# avr.net
KiCad netlist of a schematic drawn in EAGLE
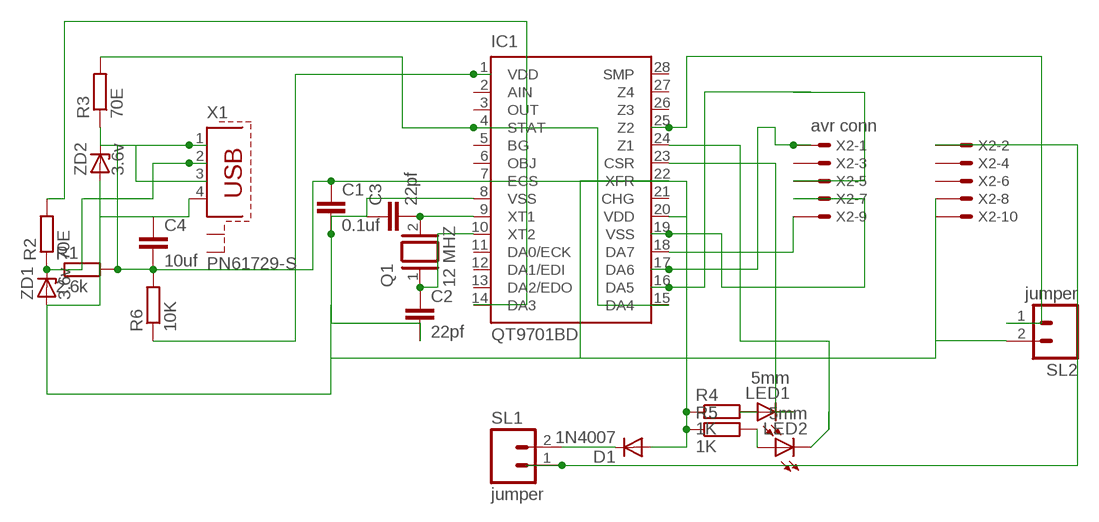
[diagram p0: schematic, sheet 1]

(export (version "E")
  (design (tool "Eeschema 10.0.6"))
  (components
    (comp (ref "C1")
      (value "0.1uf")
      (footprint "eagle-import:C2.5-3")
      (libsource (lib "eagle-import") (part "C2,5-3"))
    )
    (comp (ref "C2")
      (value "22pf")
      (footprint "eagle-import:C2.5-3")
      (libsource (lib "eagle-import") (part "C2,5-3"))
    )
    (comp (ref "C3")
      (value "22pf")
      (footprint "eagle-import:C2.5-3")
      (libsource (lib "eagle-import") (part "C2,5-3"))
    )
    (comp (ref "C4")
      (value "10uf")
      (footprint "eagle-import:C2.5-3")
      (libsource (lib "eagle-import") (part "C2,5-3"))
    )
    (comp (ref "D1")
      (value "1N4007")
      (footprint "eagle-import:DO41-10")
      (libsource (lib "eagle-import") (part "1N4004"))
    )
    (comp (ref "IC1")
      (value "QT9701BD")
      (footprint "eagle-import:DIL28-3")
      (libsource (lib "eagle-import") (part "QT9701BD"))
    )
    (comp (ref "LED1")
      (value "5mm")
      (footprint "eagle-import:LED5MM")
      (libsource (lib "eagle-import") (part "LED5MM"))
    )
    (comp (ref "LED2")
      (value "5mm")
      (footprint "eagle-import:LED5MM")
      (libsource (lib "eagle-import") (part "LED5MM"))
    )
    (comp (ref "Q1")
      (value "12 MHZ")
      (footprint "eagle-import:QS")
      (libsource (lib "eagle-import") (part "XTAL/S"))
    )
    (comp (ref "R1")
      (value "2.6k")
      (footprint "eagle-import:0204_7")
      (libsource (lib "eagle-import") (part "R-EU_0204/7"))
    )
    (comp (ref "R2")
      (value "70E")
      (footprint "eagle-import:0204_7")
      (libsource (lib "eagle-import") (part "R-EU_0204/7"))
    )
    (comp (ref "R3")
      (value "70E")
      (footprint "eagle-import:0204_7")
      (libsource (lib "eagle-import") (part "R-EU_0204/7"))
    )
    (comp (ref "R4")
      (value "1K")
      (footprint "eagle-import:0204_7")
      (libsource (lib "eagle-import") (part "R-EU_0204/7"))
    )
    (comp (ref "R5")
      (value "1K")
      (footprint "eagle-import:0204_7")
      (libsource (lib "eagle-import") (part "R-EU_0204/7"))
    )
    (comp (ref "R6")
      (value "10K")
      (footprint "eagle-import:0204_7")
      (libsource (lib "eagle-import") (part "R-EU_0204/7"))
    )
    (comp (ref "SL1")
      (value "jumper")
      (footprint "eagle-import:02P")
      (libsource (lib "eagle-import") (part "M02"))
    )
    (comp (ref "SL2")
      (value "jumper")
      (footprint "eagle-import:02P")
      (libsource (lib "eagle-import") (part "M02"))
    )
    (comp (ref "X1")
      (value "PN61729-S")
      (footprint "eagle-import:PN61729-S")
      (libsource (lib "eagle-import") (part "PN61729-S"))
    )
    (comp (ref "X2")
      (value "avr conn")
      (footprint "eagle-import:057-010-1")
      (libsource (lib "eagle-import") (part "057-010-1"))
    )
    (comp (ref "ZD1")
      (value "3.6v")
      (footprint "eagle-import:SOD81")
      (libsource (lib "eagle-import") (part "BZD23"))
    )
    (comp (ref "ZD2")
      (value "3.6v")
      (footprint "eagle-import:SOD81")
      (libsource (lib "eagle-import") (part "BZD23"))
    )
  )
  (nets
    (net (code "1") (name "Net-(D1-PadC)") (class "Default")
      (node (ref "D1") (pin "C") (pinfunction "C_C") (pintype "passive"))
      (node (ref "SL1") (pin "2") (pinfunction "2_2") (pintype "passive"))
    )
    (net (code "2") (name "Net-(IC1-CSR)") (class "Default")
      (node (ref "IC1") (pin "23") (pinfunction "CSR_23") (pintype "output"))
      (node (ref "LED1") (pin "K") (pinfunction "C_K") (pintype "passive"))
    )
    (net (code "3") (name "Net-(IC1-DA3)") (class "Default")
      (node (ref "IC1") (pin "14") (pinfunction "DA3_14") (pintype "output"))
      (node (ref "R2") (pin "2") (pinfunction "2_2") (pintype "passive"))
    )
    (net (code "4") (name "Net-(IC1-DA4)") (class "Default")
      (node (ref "IC1") (pin "15") (pinfunction "DA4_15") (pintype "output"))
      (node (ref "IC1") (pin "4") (pinfunction "STAT_4") (pintype "output"))
      (node (ref "R3") (pin "2") (pinfunction "2_2") (pintype "passive"))
    )
    (net (code "5") (name "Net-(IC1-DA5)") (class "Default")
      (node (ref "IC1") (pin "16") (pinfunction "DA5_16") (pintype "output"))
      (node (ref "X2") (pin "5") (pinfunction "S_5") (pintype "passive"))
    )
    (net (code "6") (name "Net-(IC1-DA6)") (class "Default")
      (node (ref "IC1") (pin "17") (pinfunction "DA6_17") (pintype "output"))
      (node (ref "X2") (pin "1") (pinfunction "S_1") (pintype "passive"))
    )
    (net (code "7") (name "Net-(IC1-DA7)") (class "Default")
      (node (ref "IC1") (pin "18") (pinfunction "DA7_18") (pintype "output"))
      (node (ref "X2") (pin "9") (pinfunction "S_9") (pintype "passive"))
    )
    (net (code "8") (name "Net-(IC1-ECS)") (class "Default")
      (node (ref "C1") (pin "1") (pinfunction "1_1") (pintype "passive"))
      (node (ref "C4") (pin "2") (pinfunction "2_2") (pintype "passive"))
      (node (ref "D1") (pin "A") (pinfunction "A_A") (pintype "passive"))
      (node (ref "IC1") (pin "20") (pinfunction "VDD_20") (pintype "input"))
      (node (ref "IC1") (pin "7") (pinfunction "ECS_7") (pintype "output"))
      (node (ref "R1") (pin "2") (pinfunction "2_2") (pintype "passive"))
      (node (ref "R4") (pin "1") (pinfunction "1_1") (pintype "passive"))
      (node (ref "R5") (pin "1") (pinfunction "1_1") (pintype "passive"))
      (node (ref "R6") (pin "2") (pinfunction "2_2") (pintype "passive"))
      (node (ref "X1") (pin "1") (pinfunction "1_1") (pintype "passive"))
    )
    (net (code "9") (name "Net-(IC1-VDD-Pad1)") (class "Default")
      (node (ref "IC1") (pin "1") (pinfunction "VDD_1") (pintype "input"))
      (node (ref "R6") (pin "1") (pinfunction "1_1") (pintype "passive"))
    )
    (net (code "10") (name "Net-(IC1-XFR)") (class "Default")
      (node (ref "C1") (pin "2") (pinfunction "2_2") (pintype "passive"))
      (node (ref "C2") (pin "2") (pinfunction "2_2") (pintype "passive"))
      (node (ref "C3") (pin "1") (pinfunction "1_1") (pintype "passive"))
      (node (ref "C4") (pin "1") (pinfunction "1_1") (pintype "passive"))
      (node (ref "IC1") (pin "22") (pinfunction "XFR_22") (pintype "output"))
      (node (ref "IC1") (pin "8") (pinfunction "VSS_8") (pintype "input"))
      (node (ref "SL2") (pin "2") (pinfunction "2_2") (pintype "passive"))
      (node (ref "X1") (pin "4") (pinfunction "4_4") (pintype "passive"))
      (node (ref "X2") (pin "10") (pinfunction "S_10") (pintype "passive"))
      (node (ref "X2") (pin "8") (pinfunction "S_8") (pintype "passive"))
      (node (ref "ZD1") (pin "A") (pinfunction "A_A") (pintype "passive"))
      (node (ref "ZD2") (pin "A") (pinfunction "A_A") (pintype "passive"))
    )
    (net (code "11") (name "Net-(IC1-XT1)") (class "Default")
      (node (ref "C3") (pin "2") (pinfunction "2_2") (pintype "passive"))
      (node (ref "IC1") (pin "9") (pinfunction "XT1_9") (pintype "input"))
      (node (ref "Q1") (pin "2") (pinfunction "2_2") (pintype "passive"))
    )
    (net (code "12") (name "Net-(IC1-XT2)") (class "Default")
      (node (ref "C2") (pin "1") (pinfunction "1_1") (pintype "passive"))
      (node (ref "IC1") (pin "10") (pinfunction "XT2_10") (pintype "output"))
      (node (ref "Q1") (pin "1") (pinfunction "1_1") (pintype "passive"))
    )
    (net (code "13") (name "Net-(IC1-Z1)") (class "Default")
      (node (ref "IC1") (pin "24") (pinfunction "Z1_24") (pintype "output"))
      (node (ref "LED2") (pin "K") (pinfunction "C_K") (pintype "passive"))
    )
    (net (code "14") (name "Net-(IC1-Z2)") (class "Default")
      (node (ref "IC1") (pin "25") (pinfunction "Z2_25") (pintype "output"))
      (node (ref "SL2") (pin "1") (pinfunction "1_1") (pintype "passive"))
    )
    (net (code "15") (name "Net-(LED1-PadA)") (class "Default")
      (node (ref "LED1") (pin "A") (pinfunction "A_A") (pintype "passive"))
      (node (ref "R4") (pin "2") (pinfunction "2_2") (pintype "passive"))
    )
    (net (code "16") (name "Net-(LED2-PadA)") (class "Default")
      (node (ref "LED2") (pin "A") (pinfunction "A_A") (pintype "passive"))
      (node (ref "R5") (pin "2") (pinfunction "2_2") (pintype "passive"))
    )
    (net (code "17") (name "Net-(R1-Pad1)") (class "Default")
      (node (ref "R1") (pin "1") (pinfunction "1_1") (pintype "passive"))
      (node (ref "R2") (pin "1") (pinfunction "1_1") (pintype "passive"))
      (node (ref "X1") (pin "2") (pinfunction "2_2") (pintype "passive"))
      (node (ref "ZD1") (pin "C") (pinfunction "C_C") (pintype "passive"))
    )
    (net (code "18") (name "Net-(R3-Pad1)") (class "Default")
      (node (ref "R3") (pin "1") (pinfunction "1_1") (pintype "passive"))
      (node (ref "X1") (pin "3") (pinfunction "3_3") (pintype "passive"))
      (node (ref "ZD2") (pin "C") (pinfunction "C_C") (pintype "passive"))
    )
    (net (code "19") (name "Net-(X2C-S)") (class "Default")
      (node (ref "SL1") (pin "1") (pinfunction "1_1") (pintype "passive"))
      (node (ref "X2") (pin "2") (pinfunction "S_2") (pintype "passive"))
    )
    (net (code "20") (name "Net-(X2H-S)") (class "Default")
      (node (ref "IC1") (pin "19") (pinfunction "VSS_19") (pintype "input"))
      (node (ref "X2") (pin "7") (pinfunction "S_7") (pintype "passive"))
    )
    (net (code "21") (name "unconnected-(IC1-AIN-Pad2)") (class "Default")
      (node (ref "IC1") (pin "2") (pinfunction "AIN_2") (pintype "input"))
    )
    (net (code "22") (name "unconnected-(IC1-BG-Pad5)") (class "Default")
      (node (ref "IC1") (pin "5") (pinfunction "BG_5") (pintype "input"))
    )
    (net (code "23") (name "unconnected-(IC1-CHG-Pad21)") (class "Default")
      (node (ref "IC1") (pin "21") (pinfunction "CHG_21") (pintype "output"))
    )
    (net (code "24") (name "unconnected-(IC1-DA0{slash}ECK-Pad11)") (class "Default")
      (node (ref "IC1") (pin "11") (pinfunction "DA0/ECK_11") (pintype "output"))
    )
    (net (code "25") (name "unconnected-(IC1-DA1{slash}EDI-Pad12)") (class "Default")
      (node (ref "IC1") (pin "12") (pinfunction "DA1/EDI_12") (pintype "output"))
    )
    (net (code "26") (name "unconnected-(IC1-DA2{slash}EDO-Pad13)") (class "Default")
      (node (ref "IC1") (pin "13") (pinfunction "DA2/EDO_13") (pintype "output"))
    )
    (net (code "27") (name "unconnected-(IC1-OBJ-Pad6)") (class "Default")
      (node (ref "IC1") (pin "6") (pinfunction "OBJ_6") (pintype "input"))
    )
    (net (code "28") (name "unconnected-(IC1-OUT-Pad3)") (class "Default")
      (node (ref "IC1") (pin "3") (pinfunction "OUT_3") (pintype "output"))
    )
    (net (code "29") (name "unconnected-(IC1-SMP-Pad28)") (class "Default")
      (node (ref "IC1") (pin "28") (pinfunction "SMP_28") (pintype "output"))
    )
    (net (code "30") (name "unconnected-(IC1-Z3-Pad26)") (class "Default")
      (node (ref "IC1") (pin "26") (pinfunction "Z3_26") (pintype "output"))
    )
    (net (code "31") (name "unconnected-(IC1-Z4-Pad27)") (class "Default")
      (node (ref "IC1") (pin "27") (pinfunction "Z4_27") (pintype "output"))
    )
    (net (code "32") (name "unconnected-(X1-PadS1)") (class "Default")
      (node (ref "X1") (pin "S1") (pinfunction "S1_S1") (pintype "passive"))
    )
    (net (code "33") (name "unconnected-(X1-PadS2)") (class "Default")
      (node (ref "X1") (pin "S2") (pinfunction "S2_S2") (pintype "passive"))
    )
    (net (code "34") (name "unconnected-(X2D-S-Pad3)") (class "Default")
      (node (ref "X2") (pin "3") (pinfunction "S_3") (pintype "passive"))
    )
    (net (code "35") (name "unconnected-(X2E-S-Pad4)") (class "Default")
      (node (ref "X2") (pin "4") (pinfunction "S_4") (pintype "passive"))
    )
    (net (code "36") (name "unconnected-(X2G-S-Pad6)") (class "Default")
      (node (ref "X2") (pin "6") (pinfunction "S_6") (pintype "passive"))
    )
  )
)
